# pca63100_mcu.net
KiCad netlist of a schematic drawn in Altium Designer
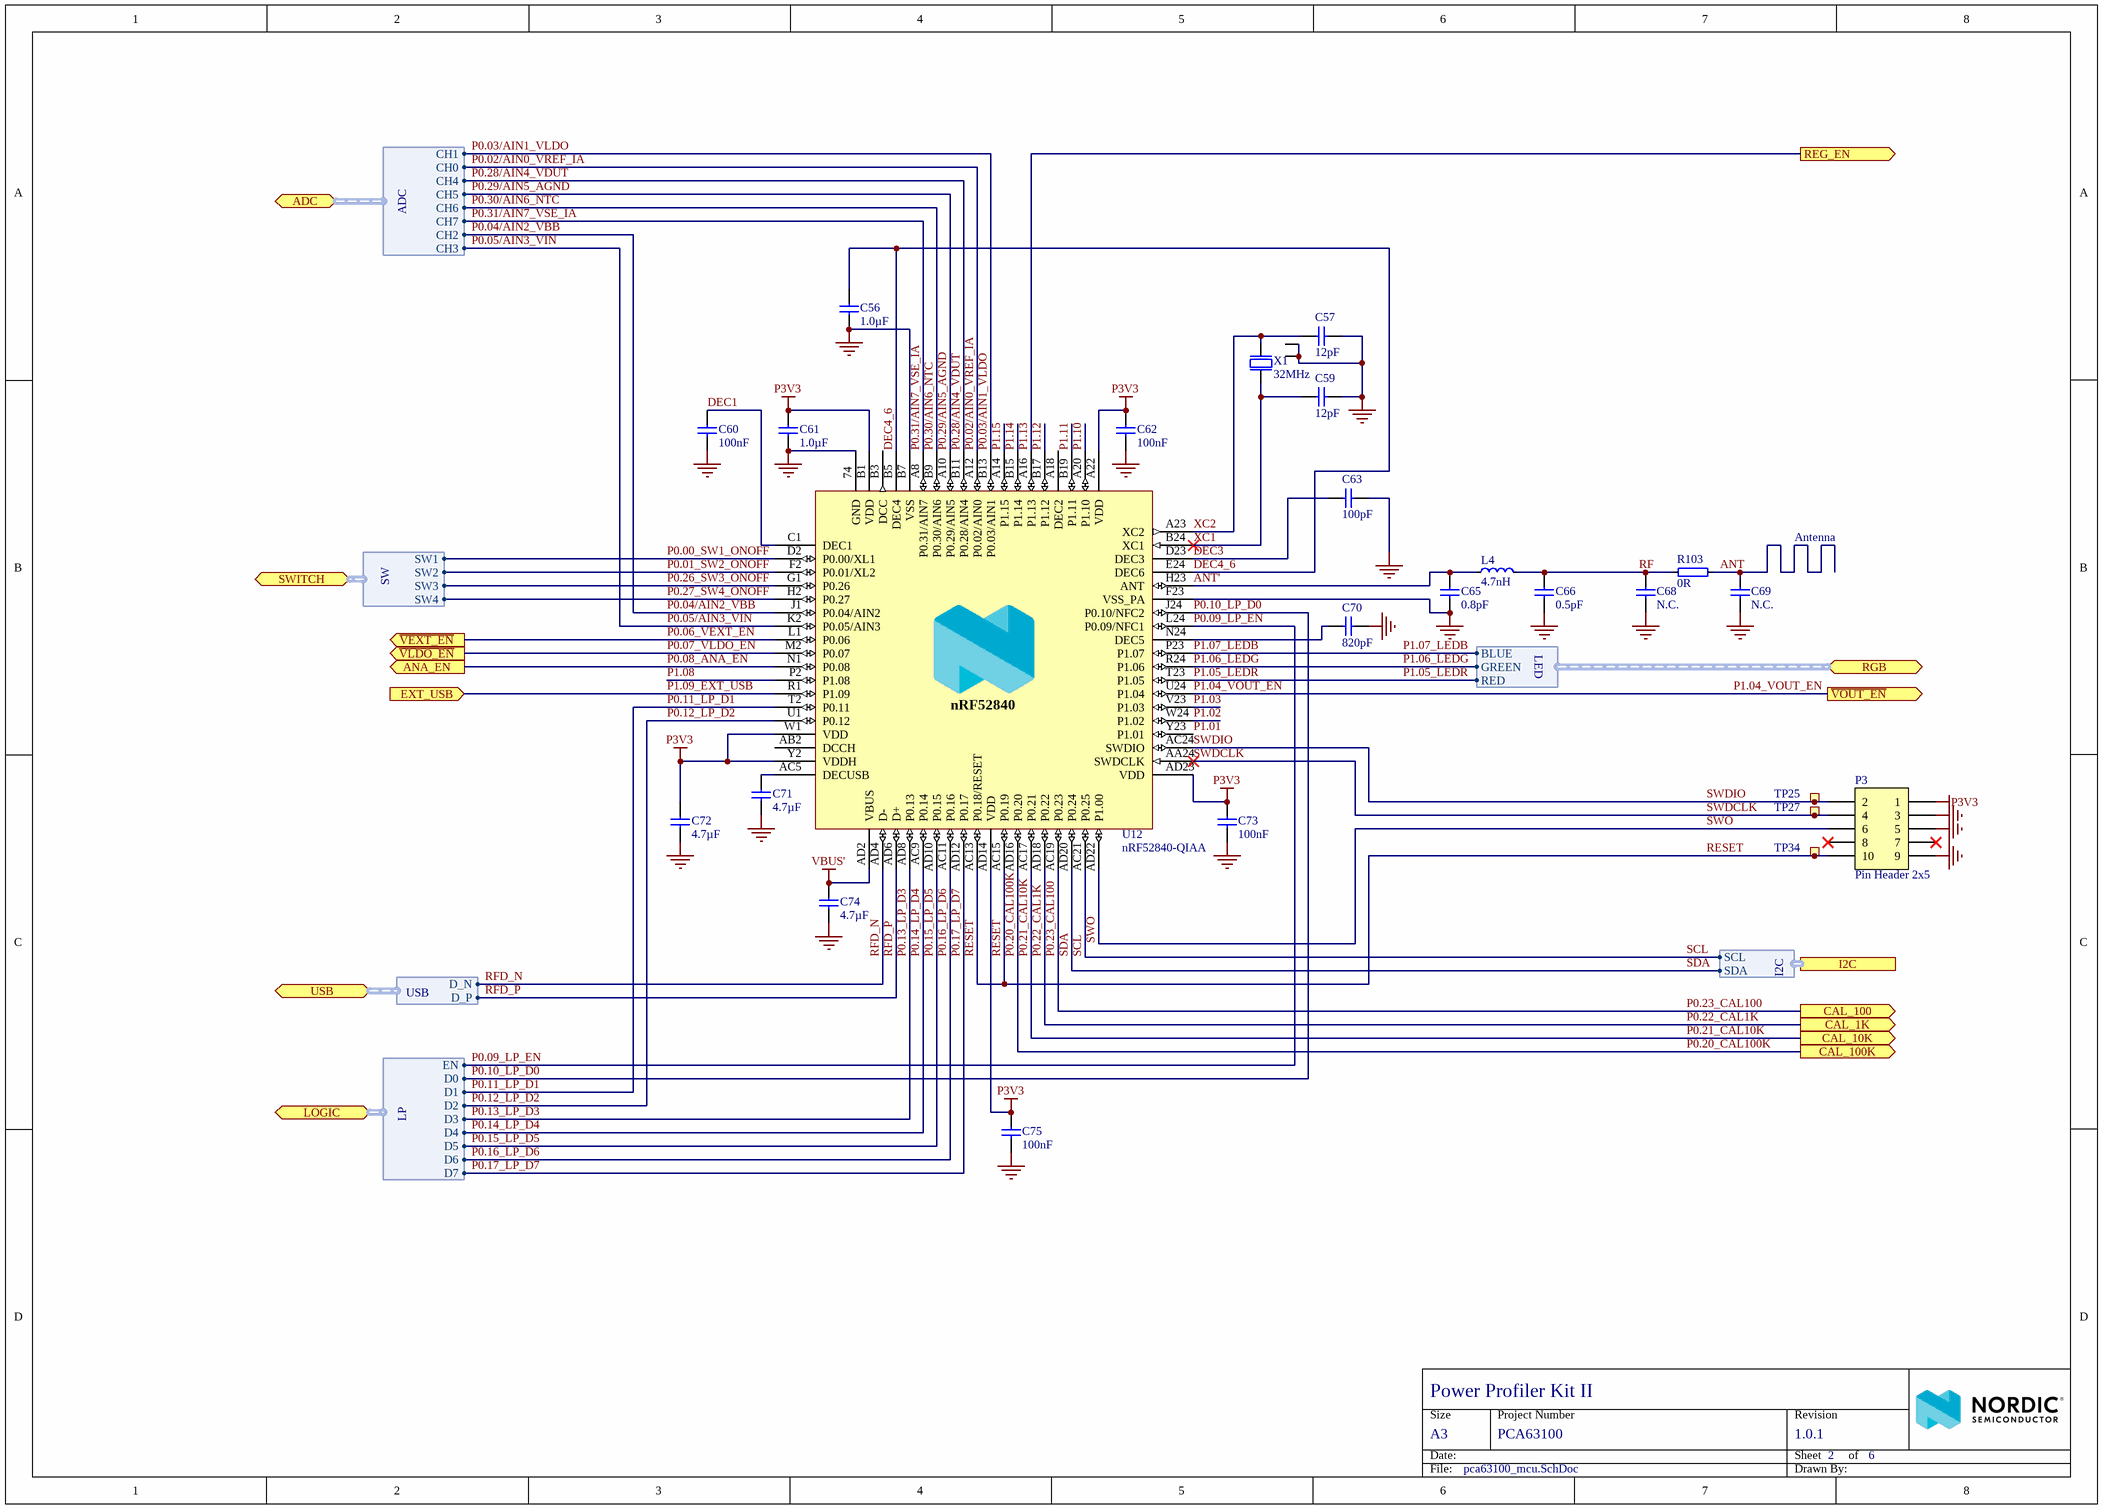
[diagram p0: pca63100_mcu.SchDoc]

(export (version "E")
  (design (tool "Eeschema 10.0.6"))
  (components
    (comp (ref "C56")
      (value "1.0µF")
      (footprint "CAPC1005X04L")
      (description "Capacitor, X5R, ±5%, 6.3V")
      (fields (field (name "PART NUMBER") "C0402-1µ0") (field (name "PUBLISHER") "Nordic Semiconductor"))
      (libsource (lib "AltiumLib") (part "CAP"))
    )
    (comp (ref "C57")
      (value "12pF")
      (footprint "CAPC1005X04L")
      (description "Capacitor, NP0, ±2%")
      (fields (field (name "PART NUMBER") "C0402-12p") (field (name "PUBLISHER") "Nordic Semiconductor"))
      (libsource (lib "AltiumLib") (part "CAP"))
    )
    (comp (ref "C59")
      (value "12pF")
      (footprint "CAPC1005X04L")
      (description "Capacitor, NP0, ±2%")
      (fields (field (name "PART NUMBER") "C0402-12p") (field (name "PUBLISHER") "Nordic Semiconductor"))
      (libsource (lib "AltiumLib") (part "CAP"))
    )
    (comp (ref "C60")
      (value "100nF")
      (footprint "CAPC0603X03L_C")
      (description "Capacitor, X5R, ±10%")
      (fields (field (name "PART NUMBER") "C0201-100n") (field (name "PUBLISHER") "Nordic Semiconductor"))
      (libsource (lib "AltiumLib") (part "CAP"))
    )
    (comp (ref "C61")
      (value "1.0µF")
      (footprint "CAPC1005X04L")
      (description "Capacitor, X5R, ±5%, 6.3V")
      (fields (field (name "PART NUMBER") "C0402-1µ0") (field (name "PUBLISHER") "Nordic Semiconductor"))
      (libsource (lib "AltiumLib") (part "CAP"))
    )
    (comp (ref "C62")
      (value "100nF")
      (footprint "CAPC0603X03L_C")
      (description "Capacitor, X5R, ±10%")
      (fields (field (name "PART NUMBER") "C0201-100n") (field (name "PUBLISHER") "Nordic Semiconductor"))
      (libsource (lib "AltiumLib") (part "CAP"))
    )
    (comp (ref "C63")
      (value "100pF")
      (footprint "CAPC0603X03L_C")
      (description "Capacitor, NP0, ±2%, 25V")
      (fields
        (field (name "PART NUMBER") "C0201-100p")
        (field (name "MANUFACTURER") "Murata")
        (field (name "PUBLISHER") "Nordic Semiconductor")
      )
      (libsource (lib "AltiumLib") (part "CAP"))
    )
    (comp (ref "C65")
      (value "0.8pF")
      (footprint "CAPC1005X04L")
      (description "Capacitor, NP0, ±5%")
      (fields
        (field (name "PART NUMBER") "C0402-0.8p")
        (field (name "MANUFACTURER") "Murata")
        (field (name "PUBLISHER") "Nordic Semiconductor")
      )
      (libsource (lib "AltiumLib") (part "CAP"))
    )
    (comp (ref "C66")
      (value "0.5pF")
      (footprint "CAPC1005X04L")
      (description "Capacitor, NP0, ±0.05pF")
      (fields
        (field (name "PART NUMBER") "C0402-0.5p")
        (field (name "MANUFACTURER") "Murata")
        (field (name "PUBLISHER") "Nordic Semiconductor")
      )
      (libsource (lib "AltiumLib") (part "CAP"))
    )
    (comp (ref "C68")
      (value "N.C.")
      (footprint "CAPC1005X04L_NC")
      (description "Not mounted")
      (fields (field (name "PART NUMBER") "C0402-N.C.") (field (name "PUBLISHER") "Nordic Semiconductor"))
      (libsource (lib "AltiumLib") (part "CAP"))
    )
    (comp (ref "C69")
      (value "N.C.")
      (footprint "CAPC1005X04L_NC")
      (description "Not mounted")
      (fields (field (name "PART NUMBER") "C0402-N.C.") (field (name "PUBLISHER") "Nordic Semiconductor"))
      (libsource (lib "AltiumLib") (part "CAP"))
    )
    (comp (ref "C70")
      (value "820pF")
      (footprint "CAPC1005X04L")
      (description "Capacitor, NP0, ±5%")
      (fields (field (name "PART NUMBER") "C0402-820p") (field (name "PUBLISHER") "Nordic Semiconductor"))
      (libsource (lib "AltiumLib") (part "CAP"))
    )
    (comp (ref "C71")
      (value "4.7µF")
      (footprint "CAPC1005X04L")
      (description "Capacitor, X5R, ±20%")
      (fields (field (name "PART NUMBER") "C0402-4µ7") (field (name "PUBLISHER") "Nordic Semiconductor"))
      (libsource (lib "AltiumLib") (part "CAP"))
    )
    (comp (ref "C72")
      (value "4.7µF")
      (footprint "CAPC1005X04L")
      (description "Capacitor, X5R, ±20%")
      (fields (field (name "PART NUMBER") "C0402-4µ7") (field (name "PUBLISHER") "Nordic Semiconductor"))
      (libsource (lib "AltiumLib") (part "CAP"))
    )
    (comp (ref "C73")
      (value "100nF")
      (footprint "CAPC0603X03L_C")
      (description "Capacitor, X5R, ±10%")
      (fields (field (name "PART NUMBER") "C0201-100n") (field (name "PUBLISHER") "Nordic Semiconductor"))
      (libsource (lib "AltiumLib") (part "CAP"))
    )
    (comp (ref "C74")
      (value "4.7µF")
      (footprint "CAPC1005X04L")
      (description "Capacitor, X5R, ±20%")
      (fields (field (name "PART NUMBER") "C0402-4µ7") (field (name "PUBLISHER") "Nordic Semiconductor"))
      (libsource (lib "AltiumLib") (part "CAP"))
    )
    (comp (ref "C75")
      (value "100nF")
      (footprint "CAPC0603X03L_C")
      (description "Capacitor, X5R, ±10%")
      (fields (field (name "PART NUMBER") "C0201-100n") (field (name "PUBLISHER") "Nordic Semiconductor"))
      (libsource (lib "AltiumLib") (part "CAP"))
    )
    (comp (ref "L4")
      (value "4.7nH")
      (footprint "INDC1005X04L")
      (description "Inductor, 160mA, ±0.1nH")
      (fields
        (field (name "PART NUMBER") "L0402-4n7")
        (field (name "MANUFACTURER") "Murata")
        (field (name "PUBLISHER") "Nordic Semiconductor")
      )
      (libsource (lib "AltiumLib") (part "IND"))
    )
    (comp (ref "P3")
      (value "Pin Header 2x5")
      (footprint "HDR_2x5-SMD-1.27mm-ANG")
      (description "Pin Header 2x5, 1.27mm (50mil)")
      (fields
        (field (name "PART NUMBER") "Pin Header 2x5 SMD, 1.27mm, Angled")
        (field (name "MANUFACTURER") "W-CON")
        (field (name "PUBLISHER") "Nordic Semiconductor")
      )
      (libsource (lib "AltiumLib") (part "CONN-2x5"))
    )
    (comp (ref "R103")
      (value "0R")
      (footprint "RESC1005X04L")
      (description "Resistor, ±5%, 0.063W")
      (fields (field (name "PART NUMBER") "R0402-0R") (field (name "PUBLISHER") "Nordic Semiconductor"))
      (libsource (lib "AltiumLib") (part "RES"))
    )
    (comp (ref "TP25")
      (value "Ø1.5mm,SMD")
      (footprint "TP_SMD_Ø1.5mm")
      (description "1.5mm circular SMD testpad")
      (fields
        (field (name "PART NUMBER") "TP_SMD_Ø1.5MM")
        (field (name "MANUFACTURER") "Nordic Semiconductor")
        (field (name "PUBLISHER") "Nordic Semiconductor")
      )
      (libsource (lib "AltiumLib") (part "TESTPAD"))
    )
    (comp (ref "TP27")
      (value "Ø1.5mm,SMD")
      (footprint "TP_SMD_Ø1.5mm")
      (description "1.5mm circular SMD testpad")
      (fields
        (field (name "PART NUMBER") "TP_SMD_Ø1.5MM")
        (field (name "MANUFACTURER") "Nordic Semiconductor")
        (field (name "PUBLISHER") "Nordic Semiconductor")
      )
      (libsource (lib "AltiumLib") (part "TESTPAD"))
    )
    (comp (ref "TP34")
      (value "Ø1.5mm,SMD")
      (footprint "TP_SMD_Ø1.5mm")
      (description "1.5mm circular SMD testpad")
      (fields
        (field (name "PART NUMBER") "TP_SMD_Ø1.5MM")
        (field (name "MANUFACTURER") "Nordic Semiconductor")
        (field (name "PUBLISHER") "Nordic Semiconductor")
      )
      (libsource (lib "AltiumLib") (part "TESTPAD"))
    )
    (comp (ref "U12")
      (value "nRF52840-QIAA")
      (footprint "AQFN50P700X700X85_HS-74N")
      (description "Multi-protocol Bluetooth Low Energy, IEEE 802.15.4, ANT and 2.4GHz proprietary system-on-chip")
      (fields
        (field (name "PART NUMBER") "nRF52840-QIAAD0")
        (field (name "MANUFACTURER") "Nordic Semiconductor")
        (field (name "PUBLISHER") "Nordic Semiconductor")
      )
      (libsource (lib "AltiumLib") (part "nRF52840_QIAA"))
    )
    (comp (ref "X1")
      (value "32MHz")
      (footprint "BT-XTAL_2016")
      (description "XTAL SMD 2016, 32MHz, Cl=8pF, Total Tol: ±40ppm")
      (fields
        (field (name "PART NUMBER") "XTAL_SMD2016_32MHz_8pF_General")
        (field (name "PUBLISHER") "Nordic Semiconductor")
      )
      (libsource (lib "AltiumLib") (part "XTAL_4-pin_grounded"))
    )
  )
  (nets
    (net (code "7") (name "/ANT") (class "Default")
      (node (ref "C69") (pin "2") (pinfunction "2_2") (pintype "passive"))
      (node (ref "R103") (pin "2") (pinfunction "2_2") (pintype "passive"))
    )
    (net (code "8") (name "/ANT'") (class "Default")
      (node (ref "C65") (pin "2") (pinfunction "2_2") (pintype "passive"))
      (node (ref "L4") (pin "1") (pinfunction "1_1") (pintype "passive"))
      (node (ref "U12") (pin "H23") (pinfunction "ANT_H23") (pintype "bidirectional"))
    )
    (net (code "9") (name "/DEC1") (class "Default")
      (node (ref "C60") (pin "1") (pinfunction "1_1") (pintype "passive"))
      (node (ref "U12") (pin "C1") (pinfunction "DEC1_C1") (pintype "power_in"))
    )
    (net (code "10") (name "/DEC3") (class "Default")
      (node (ref "C63") (pin "1") (pinfunction "1_1") (pintype "passive"))
      (node (ref "U12") (pin "D23") (pinfunction "DEC3_D23") (pintype "power_in"))
    )
    (net (code "11") (name "/DEC4_6") (class "Default")
      (node (ref "C56") (pin "2") (pinfunction "2_2") (pintype "passive"))
      (node (ref "U12") (pin "B5") (pinfunction "DEC4_B5") (pintype "power_in"))
      (node (ref "U12") (pin "E24") (pinfunction "DEC6_E24") (pintype "power_in"))
    )
    (net (code "12") (name "/P0.00_SW1_ONOFF") (class "Default")
      (node (ref "U12") (pin "D2") (pinfunction "P0.00/XL1_D2") (pintype "bidirectional"))
    )
    (net (code "13") (name "/P0.01_SW2_ONOFF") (class "Default")
      (node (ref "U12") (pin "F2") (pinfunction "P0.01/XL2_F2") (pintype "bidirectional"))
    )
    (net (code "14") (name "/P0.02{slash}AIN0_VREF_IA") (class "Default")
      (node (ref "U12") (pin "A12") (pinfunction "P0.02/AIN0_A12") (pintype "bidirectional"))
    )
    (net (code "15") (name "/P0.03{slash}AIN1_VLDO") (class "Default")
      (node (ref "U12") (pin "B13") (pinfunction "P0.03/AIN1_B13") (pintype "bidirectional"))
    )
    (net (code "16") (name "/P0.04{slash}AIN2_VBB") (class "Default")
      (node (ref "U12") (pin "J1") (pinfunction "P0.04/AIN2_J1") (pintype "bidirectional"))
    )
    (net (code "17") (name "/P0.05{slash}AIN3_VIN") (class "Default")
      (node (ref "U12") (pin "K2") (pinfunction "P0.05/AIN3_K2") (pintype "bidirectional"))
    )
    (net (code "18") (name "/P0.06_VEXT_EN") (class "Default")
      (node (ref "U12") (pin "L1") (pinfunction "P0.06_L1") (pintype "bidirectional"))
    )
    (net (code "19") (name "/P0.07_VLDO_EN") (class "Default")
      (node (ref "U12") (pin "M2") (pinfunction "P0.07_M2") (pintype "bidirectional"))
    )
    (net (code "20") (name "/P0.08_ANA_EN") (class "Default")
      (node (ref "U12") (pin "N1") (pinfunction "P0.08_N1") (pintype "bidirectional"))
    )
    (net (code "21") (name "/P0.09_LP_EN") (class "Default")
      (node (ref "U12") (pin "L24") (pinfunction "P0.09/NFC1_L24") (pintype "bidirectional"))
    )
    (net (code "22") (name "/P0.10_LP_D0") (class "Default")
      (node (ref "U12") (pin "J24") (pinfunction "P0.10/NFC2_J24") (pintype "bidirectional"))
    )
    (net (code "23") (name "/P0.11_LP_D1") (class "Default")
      (node (ref "U12") (pin "T2") (pinfunction "P0.11_T2") (pintype "bidirectional"))
    )
    (net (code "24") (name "/P0.12_LP_D2") (class "Default")
      (node (ref "U12") (pin "U1") (pinfunction "P0.12_U1") (pintype "bidirectional"))
    )
    (net (code "25") (name "/P0.13_LP_D3") (class "Default")
      (node (ref "U12") (pin "AD8") (pinfunction "P0.13_AD8") (pintype "bidirectional"))
    )
    (net (code "26") (name "/P0.14_LP_D4") (class "Default")
      (node (ref "U12") (pin "AC9") (pinfunction "P0.14_AC9") (pintype "bidirectional"))
    )
    (net (code "27") (name "/P0.15_LP_D5") (class "Default")
      (node (ref "U12") (pin "AD10") (pinfunction "P0.15_AD10") (pintype "bidirectional"))
    )
    (net (code "28") (name "/P0.16_LP_D6") (class "Default")
      (node (ref "U12") (pin "AC11") (pinfunction "P0.16_AC11") (pintype "bidirectional"))
    )
    (net (code "29") (name "/P0.17_LP_D7") (class "Default")
      (node (ref "U12") (pin "AD12") (pinfunction "P0.17_AD12") (pintype "bidirectional"))
    )
    (net (code "30") (name "/P0.20_CAL100K") (class "Default")
      (node (ref "U12") (pin "AD16") (pinfunction "P0.20_AD16") (pintype "bidirectional"))
    )
    (net (code "31") (name "/P0.21_CAL10K") (class "Default")
      (node (ref "U12") (pin "AC17") (pinfunction "P0.21_AC17") (pintype "bidirectional"))
    )
    (net (code "32") (name "/P0.22_CAL1K") (class "Default")
      (node (ref "U12") (pin "AD18") (pinfunction "P0.22_AD18") (pintype "bidirectional"))
    )
    (net (code "33") (name "/P0.23_CAL100") (class "Default")
      (node (ref "U12") (pin "AC19") (pinfunction "P0.23_AC19") (pintype "bidirectional"))
    )
    (net (code "34") (name "/P0.26_SW3_ONOFF") (class "Default")
      (node (ref "U12") (pin "G1") (pinfunction "P0.26_G1") (pintype "bidirectional"))
    )
    (net (code "35") (name "/P0.27_SW4_ONOFF") (class "Default")
      (node (ref "U12") (pin "H2") (pinfunction "P0.27_H2") (pintype "bidirectional"))
    )
    (net (code "36") (name "/P0.28{slash}AIN4_VDUT") (class "Default")
      (node (ref "U12") (pin "B11") (pinfunction "P0.28/AIN4_B11") (pintype "bidirectional"))
    )
    (net (code "37") (name "/P0.29{slash}AIN5_AGND") (class "Default")
      (node (ref "U12") (pin "A10") (pinfunction "P0.29/AIN5_A10") (pintype "bidirectional"))
    )
    (net (code "38") (name "/P0.30{slash}AIN6_NTC") (class "Default")
      (node (ref "U12") (pin "B9") (pinfunction "P0.30/AIN6_B9") (pintype "bidirectional"))
    )
    (net (code "39") (name "/P0.31{slash}AIN7_VSE_IA") (class "Default")
      (node (ref "U12") (pin "A8") (pinfunction "P0.31/AIN7_A8") (pintype "bidirectional"))
    )
    (net (code "40") (name "/P1.01") (class "Default")
      (node (ref "U12") (pin "Y23") (pinfunction "P1.01_Y23") (pintype "bidirectional"))
    )
    (net (code "41") (name "/P1.02") (class "Default")
      (node (ref "U12") (pin "W24") (pinfunction "P1.02_W24") (pintype "bidirectional"))
    )
    (net (code "42") (name "/P1.03") (class "Default")
      (node (ref "U12") (pin "V23") (pinfunction "P1.03_V23") (pintype "bidirectional"))
    )
    (net (code "43") (name "/P1.04_VOUT_EN") (class "Default")
      (node (ref "U12") (pin "U24") (pinfunction "P1.04_U24") (pintype "bidirectional"))
    )
    (net (code "44") (name "/P1.05_LEDR") (class "Default")
      (node (ref "U12") (pin "T23") (pinfunction "P1.05_T23") (pintype "bidirectional"))
    )
    (net (code "45") (name "/P1.06_LEDG") (class "Default")
      (node (ref "U12") (pin "R24") (pinfunction "P1.06_R24") (pintype "bidirectional"))
    )
    (net (code "46") (name "/P1.07_LEDB") (class "Default")
      (node (ref "U12") (pin "P23") (pinfunction "P1.07_P23") (pintype "bidirectional"))
    )
    (net (code "47") (name "/P1.08") (class "Default")
      (node (ref "U12") (pin "P2") (pinfunction "P1.08_P2") (pintype "bidirectional"))
    )
    (net (code "48") (name "/P1.09_EXT_USB") (class "Default")
      (node (ref "U12") (pin "R1") (pinfunction "P1.09_R1") (pintype "bidirectional"))
    )
    (net (code "49") (name "/P1.10") (class "Default")
      (node (ref "U12") (pin "A20") (pinfunction "P1.10_A20") (pintype "bidirectional"))
    )
    (net (code "50") (name "/P1.11") (class "Default")
      (node (ref "U12") (pin "B19") (pinfunction "P1.11_B19") (pintype "bidirectional"))
    )
    (net (code "51") (name "/P1.12") (class "Default")
      (node (ref "U12") (pin "B17") (pinfunction "P1.12_B17") (pintype "bidirectional"))
    )
    (net (code "52") (name "/P1.13") (class "Default")
      (node (ref "U12") (pin "A16") (pinfunction "P1.13_A16") (pintype "bidirectional"))
    )
    (net (code "53") (name "/P1.14") (class "Default")
      (node (ref "U12") (pin "B15") (pinfunction "P1.14_B15") (pintype "bidirectional"))
    )
    (net (code "54") (name "/P1.15") (class "Default")
      (node (ref "U12") (pin "A14") (pinfunction "P1.15_A14") (pintype "bidirectional"))
    )
    (net (code "55") (name "/RESET") (class "Default")
      (node (ref "P3") (pin "10") (pinfunction "10_10") (pintype "passive"))
      (node (ref "TP34") (pin "1") (pinfunction "1_1") (pintype "passive"))
      (node (ref "U12") (pin "AC13") (pinfunction "P0.18/RESET_AC13") (pintype "bidirectional"))
      (node (ref "U12") (pin "AC15") (pinfunction "P0.19_AC15") (pintype "bidirectional"))
    )
    (net (code "56") (name "/RF") (class "Default")
      (node (ref "C66") (pin "2") (pinfunction "2_2") (pintype "passive"))
      (node (ref "C68") (pin "2") (pinfunction "2_2") (pintype "passive"))
      (node (ref "L4") (pin "2") (pinfunction "2_2") (pintype "passive"))
      (node (ref "R103") (pin "1") (pinfunction "1_1") (pintype "passive"))
    )
    (net (code "57") (name "/RFD_N") (class "Default")
      (node (ref "U12") (pin "AD4") (pinfunction "D-_AD4") (pintype "bidirectional"))
    )
    (net (code "58") (name "/RFD_P") (class "Default")
      (node (ref "U12") (pin "AD6") (pinfunction "D+_AD6") (pintype "bidirectional"))
    )
    (net (code "59") (name "/SCL") (class "Default")
      (node (ref "U12") (pin "AC21") (pinfunction "P0.25_AC21") (pintype "bidirectional"))
    )
    (net (code "60") (name "/SDA") (class "Default")
      (node (ref "U12") (pin "AD20") (pinfunction "P0.24_AD20") (pintype "bidirectional"))
    )
    (net (code "61") (name "/SWDCLK") (class "Default")
      (node (ref "P3") (pin "4") (pinfunction "4_4") (pintype "passive"))
      (node (ref "TP27") (pin "1") (pinfunction "1_1") (pintype "passive"))
      (node (ref "U12") (pin "AA24") (pinfunction "SWDCLK_AA24") (pintype "input"))
    )
    (net (code "62") (name "/SWDIO") (class "Default")
      (node (ref "P3") (pin "2") (pinfunction "2_2") (pintype "passive"))
      (node (ref "TP25") (pin "1") (pinfunction "1_1") (pintype "passive"))
      (node (ref "U12") (pin "AC24") (pinfunction "SWDIO_AC24") (pintype "bidirectional"))
    )
    (net (code "63") (name "/SWO") (class "Default")
      (node (ref "P3") (pin "6") (pinfunction "6_6") (pintype "passive"))
      (node (ref "U12") (pin "AD22") (pinfunction "P1.00_AD22") (pintype "bidirectional"))
    )
    (net (code "64") (name "/XC1") (class "Default")
      (node (ref "C59") (pin "1") (pinfunction "1_1") (pintype "passive"))
      (node (ref "U12") (pin "B24") (pinfunction "XC1_B24") (pintype "input"))
      (node (ref "X1") (pin "1") (pinfunction "inp_1") (pintype "passive"))
    )
    (net (code "65") (name "/XC2") (class "Default")
      (node (ref "C57") (pin "1") (pinfunction "1_1") (pintype "passive"))
      (node (ref "U12") (pin "A23") (pinfunction "XC2_A23") (pintype "output"))
      (node (ref "X1") (pin "3") (pinfunction "out_3") (pintype "passive"))
    )
    (net (code "72") (name "GND") (class "Default")
      (node (ref "C56") (pin "1") (pinfunction "1_1") (pintype "passive"))
      (node (ref "C57") (pin "2") (pinfunction "2_2") (pintype "passive"))
      (node (ref "C59") (pin "2") (pinfunction "2_2") (pintype "passive"))
      (node (ref "C60") (pin "2") (pinfunction "2_2") (pintype "passive"))
      (node (ref "C61") (pin "2") (pinfunction "2_2") (pintype "passive"))
      (node (ref "C62") (pin "2") (pinfunction "2_2") (pintype "passive"))
      (node (ref "C63") (pin "2") (pinfunction "2_2") (pintype "passive"))
      (node (ref "C65") (pin "1") (pinfunction "1_1") (pintype "passive"))
      (node (ref "C66") (pin "1") (pinfunction "1_1") (pintype "passive"))
      (node (ref "C68") (pin "1") (pinfunction "1_1") (pintype "passive"))
      (node (ref "C69") (pin "1") (pinfunction "1_1") (pintype "passive"))
      (node (ref "C70") (pin "2") (pinfunction "2_2") (pintype "passive"))
      (node (ref "C71") (pin "2") (pinfunction "2_2") (pintype "passive"))
      (node (ref "C72") (pin "2") (pinfunction "2_2") (pintype "passive"))
      (node (ref "C73") (pin "2") (pinfunction "2_2") (pintype "passive"))
      (node (ref "C74") (pin "2") (pinfunction "2_2") (pintype "passive"))
      (node (ref "C75") (pin "2") (pinfunction "2_2") (pintype "passive"))
      (node (ref "P3") (pin "3") (pinfunction "3_3") (pintype "passive"))
      (node (ref "P3") (pin "5") (pinfunction "5_5") (pintype "passive"))
      (node (ref "P3") (pin "9") (pinfunction "9_9") (pintype "passive"))
      (node (ref "U12") (pin "74") (pinfunction "GND_74") (pintype "power_in"))
      (node (ref "U12") (pin "B7") (pinfunction "VSS_B7") (pintype "power_in"))
      (node (ref "U12") (pin "F23") (pinfunction "VSS_PA_F23") (pintype "power_in"))
      (node (ref "X1") (pin "2") (pinfunction "GND_2") (pintype "passive"))
      (node (ref "X1") (pin "4") (pinfunction "GND_4") (pintype "passive"))
    )
    (net (code "73") (name "Net-(U12-DEC5)") (class "Default")
      (node (ref "C70") (pin "1") (pinfunction "1_1") (pintype "passive"))
      (node (ref "U12") (pin "N24") (pinfunction "DEC5_N24") (pintype "power_in"))
    )
    (net (code "74") (name "Net-(U12-DECUSB)") (class "Default")
      (node (ref "C71") (pin "1") (pinfunction "1_1") (pintype "passive"))
      (node (ref "U12") (pin "AC5") (pinfunction "DECUSB_AC5") (pintype "power_in"))
    )
    (net (code "75") (name "P3V3") (class "Default")
      (node (ref "C61") (pin "1") (pinfunction "1_1") (pintype "passive"))
      (node (ref "C62") (pin "1") (pinfunction "1_1") (pintype "passive"))
      (node (ref "C72") (pin "1") (pinfunction "1_1") (pintype "passive"))
      (node (ref "C73") (pin "1") (pinfunction "1_1") (pintype "passive"))
      (node (ref "C75") (pin "1") (pinfunction "1_1") (pintype "passive"))
      (node (ref "P3") (pin "1") (pinfunction "1_1") (pintype "passive"))
      (node (ref "U12") (pin "A22") (pinfunction "VDD_A22") (pintype "power_in"))
      (node (ref "U12") (pin "AD14") (pinfunction "VDD_AD14") (pintype "power_in"))
      (node (ref "U12") (pin "AD23") (pinfunction "VDD_AD23") (pintype "power_in"))
      (node (ref "U12") (pin "B1") (pinfunction "VDD_B1") (pintype "power_in"))
      (node (ref "U12") (pin "W1") (pinfunction "VDD_W1") (pintype "power_in"))
      (node (ref "U12") (pin "Y2") (pinfunction "VDDH_Y2") (pintype "power_in"))
    )
    (net (code "76") (name "VBUS'") (class "Default")
      (node (ref "C74") (pin "1") (pinfunction "1_1") (pintype "passive"))
      (node (ref "U12") (pin "AD2") (pinfunction "VBUS_AD2") (pintype "power_in"))
    )
    (net (code "77") (name "unconnected-(P3-Pad7)") (class "Default")
      (node (ref "P3") (pin "7") (pinfunction "7_7") (pintype "passive+no_connect"))
    )
    (net (code "78") (name "unconnected-(P3-Pad8)") (class "Default")
      (node (ref "P3") (pin "8") (pinfunction "8_8") (pintype "passive+no_connect"))
    )
    (net (code "79") (name "unconnected-(U12-DCC-PadB3)") (class "Default")
      (node (ref "U12") (pin "B3") (pinfunction "DCC_B3") (pintype "output"))
    )
    (net (code "80") (name "unconnected-(U12-DCCH-PadAB2)") (class "Default")
      (node (ref "U12") (pin "AB2") (pinfunction "DCCH_AB2") (pintype "power_in"))
    )
    (net (code "81") (name "unconnected-(U12-DEC2-PadA18)") (class "Default")
      (node (ref "U12") (pin "A18") (pinfunction "DEC2_A18") (pintype "power_in"))
    )
  )
)
